# 5V_Digital_In.net
KiCad netlist of a schematic drawn in Altium Designer
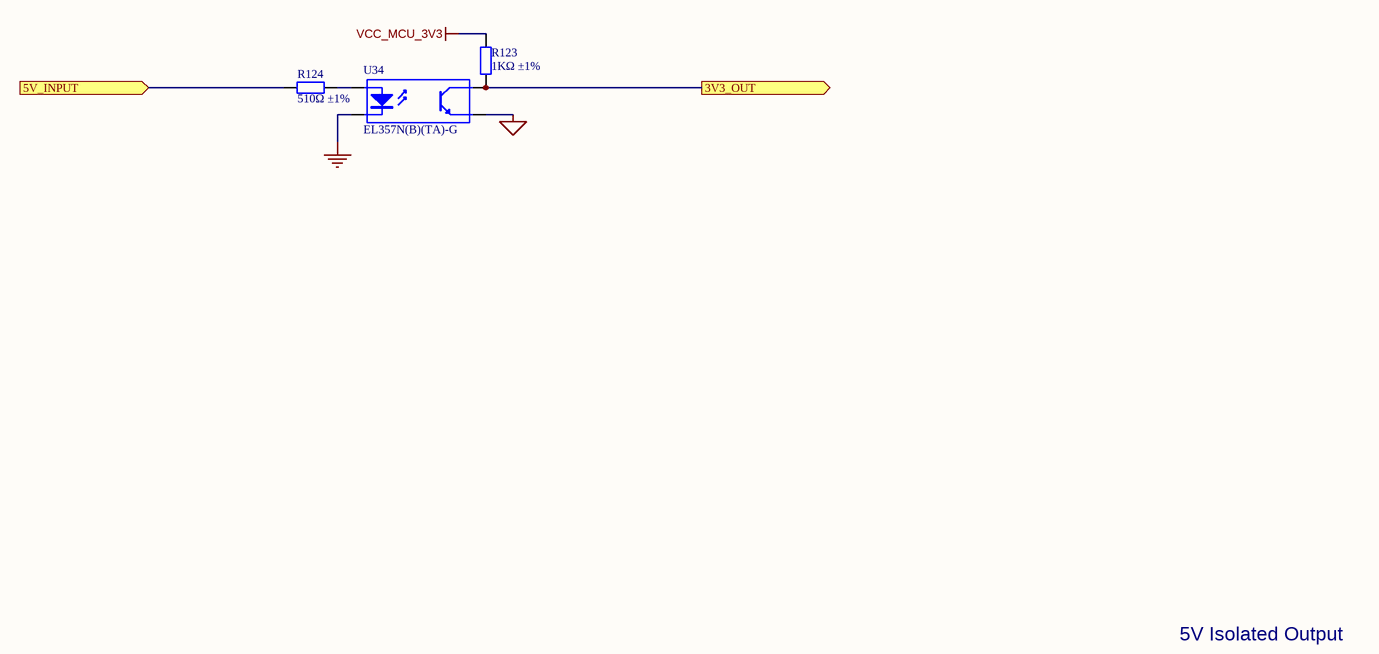
[diagram p0: 5V_Digital_In.SchDoc]

(export (version "E")
  (design (tool "Eeschema 10.0.6"))
  (components
    (comp (ref "R123")
      (value "1KΩ ±1%")
      (footprint "0603_R")
      (description "Chip resistor")
      (fields (field (name "MANUFACTURER") "Uniroyal Elec") (field (name "PARTNUMBER") "0603WAF1001T5E"))
      (libsource (lib "RES") (part "0603 1K (1001) 1%"))
    )
    (comp (ref "R124")
      (value "510Ω ±1%")
      (footprint "0603_R")
      (description "Chip resistor")
      (fields (field (name "MANUFACTURER") "Uniroyal Elec") (field (name "PARTNUMBER") "0603WAF5100T5E"))
      (libsource (lib "RES") (part "0603 510R (5100) 1%"))
    )
    (comp (ref "U34")
      (value "EL357N(B)(TA)-G")
      (footprint "Miscellaneous Devices LC:SOP-4_P2.54")
      (description "OPTOISOLATOR 3.75KV TRANS 4-SOP")
      (libsource (lib "IC") (part "EL357N(B)(TA)-G_[C6649]"))
    )
  )
  (nets
    (net (code "1") (name "/3V3_OUT") (class "Default")
      (node (ref "R123") (pin "2") (pinfunction "2_2") (pintype "passive"))
      (node (ref "U34") (pin "4") (pinfunction "C_4") (pintype "passive"))
    )
    (net (code "2") (name "/5V_INPUT") (class "Default")
      (node (ref "R124") (pin "1") (pinfunction "1_1") (pintype "passive"))
    )
    (net (code "3") (name "GND") (class "Default")
      (node (ref "U34") (pin "2") (pinfunction "K_2") (pintype "passive"))
    )
    (net (code "4") (name "MCU_GND") (class "Default")
      (node (ref "U34") (pin "3") (pinfunction "E_3") (pintype "passive"))
    )
    (net (code "5") (name "Net-(U34-A)") (class "Default")
      (node (ref "R124") (pin "2") (pinfunction "2_2") (pintype "passive"))
      (node (ref "U34") (pin "1") (pinfunction "A_1") (pintype "passive"))
    )
    (net (code "6") (name "VCC_MCU_3V3") (class "Default")
      (node (ref "R123") (pin "1") (pinfunction "1_1") (pintype "passive"))
    )
  )
)
